# switch_conn.net
KiCad netlist of a schematic drawn in Altium Designer
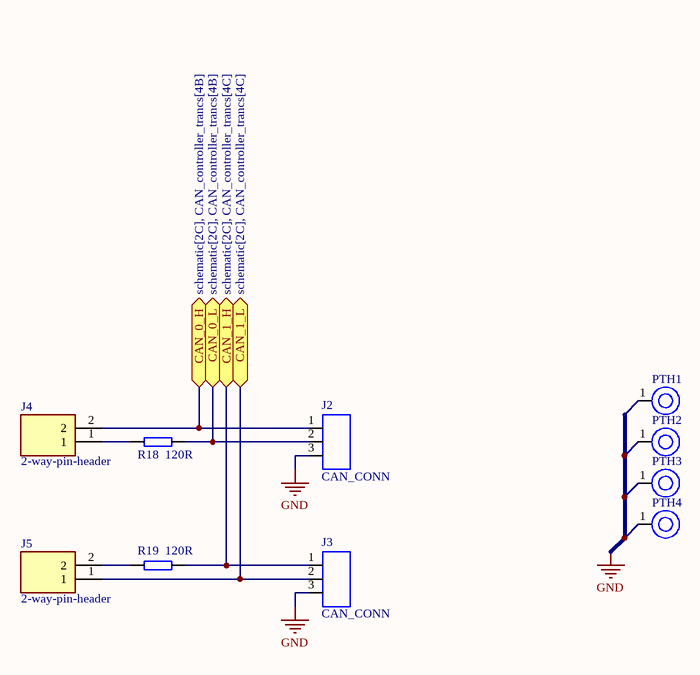
[diagram p0: switch_conn.SchDoc]

(export (version "E")
  (design (tool "Eeschema 10.0.6"))
  (components
    (comp (ref "J2") (value "CAN_CONN") (footprint "Terminal") (libsource (lib "sch_comp") (part "CAN_CONN")))
    (comp (ref "J3") (value "CAN_CONN") (footprint "Terminal") (libsource (lib "sch_comp") (part "CAN_CONN")))
    (comp (ref "J4")
      (value "2-way-pin-header")
      (footprint "HDRV2W66P0X254_1X2_508X249X1067P")
      (libsource (lib "sch_comp") (part "2-way-pin-header"))
    )
    (comp (ref "J5")
      (value "2-way-pin-header")
      (footprint "HDRV2W66P0X254_1X2_508X249X1067P")
      (libsource (lib "sch_comp") (part "2-way-pin-header"))
    )
    (comp (ref "PTH1")
      (value "PTH?")
      (footprint "mh_fp")
      (description "Mounting Hole, 2.5mm")
      (libsource (lib "sch_comp") (part "PTH?"))
    )
    (comp (ref "PTH2")
      (value "PTH?")
      (footprint "mh_fp")
      (description "Mounting Hole, 2.5mm")
      (libsource (lib "sch_comp") (part "PTH?"))
    )
    (comp (ref "PTH3")
      (value "PTH?")
      (footprint "mh_fp")
      (description "Mounting Hole, 2.5mm")
      (libsource (lib "sch_comp") (part "PTH?"))
    )
    (comp (ref "PTH4")
      (value "PTH?")
      (footprint "mh_fp")
      (description "Mounting Hole, 2.5mm")
      (libsource (lib "sch_comp") (part "PTH?"))
    )
    (comp (ref "R18") (value "120R") (footprint "RES0402") (libsource (lib "sch_comp") (part "RES 0402")))
    (comp (ref "R19") (value "120R") (footprint "RES0402") (libsource (lib "sch_comp") (part "RES 0402")))
  )
  (nets
    (net (code "1") (name "/CAN_0_H") (class "Default")
      (node (ref "J2") (pin "1") (pinfunction "CAN_H_1") (pintype "passive"))
      (node (ref "J4") (pin "2") (pinfunction "2_2") (pintype "passive"))
    )
    (net (code "2") (name "/CAN_0_L") (class "Default")
      (node (ref "J2") (pin "2") (pinfunction "22_2") (pintype "passive"))
      (node (ref "R18") (pin "1") (pintype "passive"))
    )
    (net (code "3") (name "/CAN_1_H") (class "Default")
      (node (ref "J3") (pin "1") (pinfunction "CAN_H_1") (pintype "passive"))
      (node (ref "R19") (pin "1") (pintype "passive"))
    )
    (net (code "4") (name "/CAN_1_L") (class "Default")
      (node (ref "J3") (pin "2") (pinfunction "22_2") (pintype "passive"))
      (node (ref "J5") (pin "1") (pinfunction "1_1") (pintype "passive"))
    )
    (net (code "5") (name "GND") (class "Default")
      (node (ref "J2") (pin "3") (pinfunction "23_3") (pintype "passive"))
      (node (ref "J3") (pin "3") (pinfunction "23_3") (pintype "passive"))
      (node (ref "PTH1") (pin "1") (pinfunction "1_1") (pintype "passive"))
      (node (ref "PTH2") (pin "1") (pinfunction "1_1") (pintype "passive"))
      (node (ref "PTH3") (pin "1") (pinfunction "1_1") (pintype "passive"))
      (node (ref "PTH4") (pin "1") (pinfunction "1_1") (pintype "passive"))
    )
    (net (code "6") (name "Net-(J4-Pad1)") (class "Default")
      (node (ref "J4") (pin "1") (pinfunction "1_1") (pintype "passive"))
      (node (ref "R18") (pin "2") (pintype "passive"))
    )
    (net (code "7") (name "Net-(J5-Pad2)") (class "Default")
      (node (ref "J5") (pin "2") (pinfunction "2_2") (pintype "passive"))
      (node (ref "R19") (pin "2") (pintype "passive"))
    )
  )
)
